# pthbadge_batt_non_sao.net
KiCad netlist of a schematic drawn in EAGLE
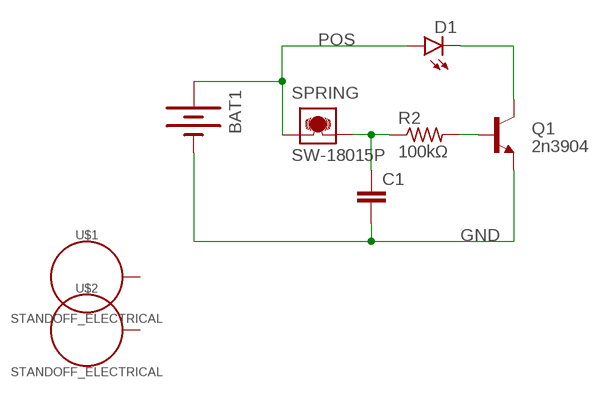
[diagram p0: schematic, sheet 1]

(export (version "E")
  (design (tool "Eeschema 10.0.6"))
  (components
    (comp (ref "BAT1")
      (value "BATTERY20PTH")
      (footprint "eagle-import:BATTCOM_20MM_PTH")
      (libsource (lib "eagle-import") (part "BATTERY20PTH"))
    )
    (comp (ref "C1")
      (value "CAPPTH")
      (footprint "eagle-import:CAP-PTH-SMALL")
      (libsource (lib "eagle-import") (part "CAPPTH"))
    )
    (comp (ref "D1")
      (value "LED5MM")
      (footprint "eagle-import:LED5MM")
      (libsource (lib "eagle-import") (part "LED5MM"))
    )
    (comp (ref "Q1")
      (value "2n3904")
      (footprint "eagle-import:TO-92")
      (libsource (lib "eagle-import") (part "TRANSISTOR_NPN2N3904"))
    )
    (comp (ref "R2")
      (value "100kΩ")
      (footprint "eagle-import:0207_10")
      (libsource (lib "eagle-import") (part "R-US_0207/10"))
    )
    (comp (ref "SPRING")
      (value "SW-18015P")
      (footprint "eagle-import:SW-18015P")
      (fields (field (name "MF") "FARNELL") (field (name "MPN") "CM4400-1."))
      (libsource (lib "eagle-import") (part "SW-18015P"))
    )
    (comp (ref "U$1")
      (value "STANDOFF_ELECTRICAL")
      (footprint "eagle-import:STANDOFF-ELECTRICAL")
      (libsource (lib "eagle-import") (part "STANDOFF_ELECTRICAL"))
    )
    (comp (ref "U$2")
      (value "STANDOFF_ELECTRICAL")
      (footprint "eagle-import:STANDOFF-ELECTRICAL")
      (libsource (lib "eagle-import") (part "STANDOFF_ELECTRICAL"))
    )
  )
  (nets
    (net (code "1") (name "/GND") (class "Default")
      (node (ref "BAT1") (pin "2") (pinfunction "-_2") (pintype "power_in"))
      (node (ref "C1") (pin "2") (pinfunction "2_2") (pintype "passive"))
      (node (ref "Q1") (pin "1") (pinfunction "E_1") (pintype "passive"))
    )
    (net (code "2") (name "/POS") (class "Default")
      (node (ref "BAT1") (pin "1") (pinfunction "+_1") (pintype "power_in"))
      (node (ref "D1") (pin "A") (pinfunction "A_A") (pintype "passive"))
      (node (ref "SPRING") (pin "1") (pinfunction "1_1") (pintype "passive"))
    )
    (net (code "3") (name "Net-(C1-Pad1)") (class "Default")
      (node (ref "C1") (pin "1") (pinfunction "1_1") (pintype "passive"))
      (node (ref "R2") (pin "1") (pinfunction "1_1") (pintype "passive"))
      (node (ref "SPRING") (pin "2") (pinfunction "2_2") (pintype "passive"))
    )
    (net (code "4") (name "Net-(D1-C)") (class "Default")
      (node (ref "D1") (pin "K") (pinfunction "C_K") (pintype "passive"))
      (node (ref "Q1") (pin "3") (pinfunction "C_3") (pintype "passive"))
    )
    (net (code "5") (name "Net-(Q1-B)") (class "Default")
      (node (ref "Q1") (pin "2") (pinfunction "B_2") (pintype "passive"))
      (node (ref "R2") (pin "2") (pinfunction "2_2") (pintype "passive"))
    )
    (net (code "6") (name "unconnected-(U$1-P$1-PadP1)") (class "Default")
      (node (ref "U$1") (pin "P1") (pinfunction "P$1_P1") (pintype "bidirectional"))
    )
    (net (code "7") (name "unconnected-(U$2-P$1-PadP1)") (class "Default")
      (node (ref "U$2") (pin "P1") (pinfunction "P$1_P1") (pintype "bidirectional"))
    )
  )
)
